# leds-and-button.net
KiCad netlist of a schematic drawn in EAGLE
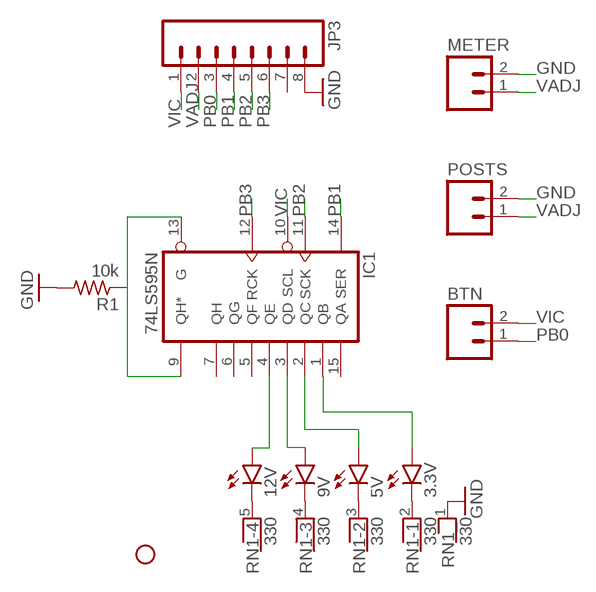
[diagram p0: schematic, sheet 1]

(export (version "E")
  (design (tool "Eeschema 10.0.6"))
  (components
    (comp (ref "3.3V")
      (value "LED3MM")
      (footprint "eagle-import:LED3MM")
      (libsource (lib "eagle-import") (part "LED3MM"))
    )
    (comp (ref "5V")
      (value "LED3MM")
      (footprint "eagle-import:LED3MM")
      (libsource (lib "eagle-import") (part "LED3MM"))
    )
    (comp (ref "9V")
      (value "LED3MM")
      (footprint "eagle-import:LED3MM")
      (libsource (lib "eagle-import") (part "LED3MM"))
    )
    (comp (ref "12V")
      (value "LED3MM")
      (footprint "eagle-import:LED3MM")
      (libsource (lib "eagle-import") (part "LED3MM"))
    )
    (comp (ref "BTN")
      (value "M02PTH")
      (footprint "eagle-import:1X02")
      (libsource (lib "eagle-import") (part "M02PTH"))
    )
    (comp (ref "IC1")
      (value "74LS595N")
      (footprint "eagle-import:DIL16")
      (libsource (lib "eagle-import") (part "74595NLS"))
    )
    (comp (ref "JP2")
      (value "STAND-OFF")
      (footprint "eagle-import:STAND-OFF")
      (libsource (lib "eagle-import") (part "STAND-OFF"))
    )
    (comp (ref "JP3")
      (value "M081X08")
      (footprint "eagle-import:1X08")
      (libsource (lib "eagle-import") (part "M081X08"))
    )
    (comp (ref "METER")
      (value "M02PTH")
      (footprint "eagle-import:1X02")
      (libsource (lib "eagle-import") (part "M02PTH"))
    )
    (comp (ref "POSTS")
      (value "M02PTH")
      (footprint "eagle-import:1X02")
      (libsource (lib "eagle-import") (part "M02PTH"))
    )
    (comp (ref "R1")
      (value "10k")
      (footprint "eagle-import:0204V")
      (libsource (lib "eagle-import") (part "R-US_0204/2V"))
    )
    (comp (ref "RN1")
      (value "330")
      (footprint "eagle-import:RN-6")
      (libsource (lib "eagle-import") (part "RNX5"))
    )
  )
  (nets
    (net (code "1") (name "/PB0") (class "Default")
      (node (ref "BTN") (pin "1") (pinfunction "1_1") (pintype "passive"))
      (node (ref "JP3") (pin "3") (pinfunction "3_3") (pintype "passive"))
    )
    (net (code "2") (name "/PB1") (class "Default")
      (node (ref "IC1") (pin "14") (pinfunction "SER_14") (pintype "input"))
      (node (ref "JP3") (pin "4") (pinfunction "4_4") (pintype "passive"))
    )
    (net (code "3") (name "/PB2") (class "Default")
      (node (ref "IC1") (pin "11") (pinfunction "SCK_11") (pintype "input"))
      (node (ref "JP3") (pin "5") (pinfunction "5_5") (pintype "passive"))
    )
    (net (code "4") (name "/PB3") (class "Default")
      (node (ref "IC1") (pin "12") (pinfunction "RCK_12") (pintype "input"))
      (node (ref "JP3") (pin "6") (pinfunction "6_6") (pintype "passive"))
    )
    (net (code "5") (name "/VADJ") (class "Default")
      (node (ref "JP3") (pin "2") (pinfunction "2_2") (pintype "passive"))
      (node (ref "METER") (pin "1") (pinfunction "1_1") (pintype "passive"))
      (node (ref "POSTS") (pin "1") (pinfunction "1_1") (pintype "passive"))
    )
    (net (code "6") (name "/VIC") (class "Default")
      (node (ref "BTN") (pin "2") (pinfunction "2_2") (pintype "passive"))
      (node (ref "IC1") (pin "10") (pinfunction "SCL_10") (pintype "input"))
      (node (ref "JP3") (pin "1") (pinfunction "1_1") (pintype "passive"))
    )
    (net (code "7") (name "GND") (class "Default")
      (node (ref "JP3") (pin "8") (pinfunction "8_8") (pintype "passive"))
      (node (ref "METER") (pin "2") (pinfunction "2_2") (pintype "passive"))
      (node (ref "POSTS") (pin "2") (pinfunction "2_2") (pintype "passive"))
      (node (ref "R1") (pin "2") (pinfunction "2_2") (pintype "passive"))
      (node (ref "RN1") (pin "1") (pinfunction "1_1") (pintype "passive"))
    )
    (net (code "8") (name "Net-(3.3V-C)") (class "Default")
      (node (ref "3.3V") (pin "K") (pinfunction "C_K") (pintype "passive"))
      (node (ref "RN1") (pin "2") (pinfunction "1_2") (pintype "passive"))
    )
    (net (code "9") (name "Net-(5V-C)") (class "Default")
      (node (ref "5V") (pin "K") (pinfunction "C_K") (pintype "passive"))
      (node (ref "RN1") (pin "3") (pinfunction "1_3") (pintype "passive"))
    )
    (net (code "10") (name "Net-(9V-C)") (class "Default")
      (node (ref "9V") (pin "K") (pinfunction "C_K") (pintype "passive"))
      (node (ref "RN1") (pin "4") (pinfunction "1_4") (pintype "passive"))
    )
    (net (code "11") (name "Net-(12V-C)") (class "Default")
      (node (ref "12V") (pin "K") (pinfunction "C_K") (pintype "passive"))
      (node (ref "RN1") (pin "5") (pinfunction "1_5") (pintype "passive"))
    )
    (net (code "12") (name "Net-(IC1A-G)") (class "Default")
      (node (ref "IC1") (pin "13") (pinfunction "G_13") (pintype "input"))
      (node (ref "IC1") (pin "9") (pinfunction "QH*_9") (pintype "tri_state"))
      (node (ref "R1") (pin "1") (pinfunction "1_1") (pintype "passive"))
    )
    (net (code "13") (name "Net-(IC1A-QB)") (class "Default")
      (node (ref "3.3V") (pin "A") (pinfunction "A_A") (pintype "passive"))
      (node (ref "IC1") (pin "1") (pinfunction "QB_1") (pintype "tri_state"))
    )
    (net (code "14") (name "Net-(IC1A-QC)") (class "Default")
      (node (ref "5V") (pin "A") (pinfunction "A_A") (pintype "passive"))
      (node (ref "IC1") (pin "2") (pinfunction "QC_2") (pintype "tri_state"))
    )
    (net (code "15") (name "Net-(IC1A-QD)") (class "Default")
      (node (ref "9V") (pin "A") (pinfunction "A_A") (pintype "passive"))
      (node (ref "IC1") (pin "3") (pinfunction "QD_3") (pintype "tri_state"))
    )
    (net (code "16") (name "Net-(IC1A-QE)") (class "Default")
      (node (ref "12V") (pin "A") (pinfunction "A_A") (pintype "passive"))
      (node (ref "IC1") (pin "4") (pinfunction "QE_4") (pintype "tri_state"))
    )
    (net (code "17") (name "unconnected-(IC1A-QA-Pad15)") (class "Default")
      (node (ref "IC1") (pin "15") (pinfunction "QA_15") (pintype "tri_state"))
    )
    (net (code "18") (name "unconnected-(IC1A-QF-Pad5)") (class "Default")
      (node (ref "IC1") (pin "5") (pinfunction "QF_5") (pintype "tri_state"))
    )
    (net (code "19") (name "unconnected-(IC1A-QG-Pad6)") (class "Default")
      (node (ref "IC1") (pin "6") (pinfunction "QG_6") (pintype "tri_state"))
    )
    (net (code "20") (name "unconnected-(IC1A-QH-Pad7)") (class "Default")
      (node (ref "IC1") (pin "7") (pinfunction "QH_7") (pintype "tri_state"))
    )
    (net (code "21") (name "unconnected-(JP3-Pad7)") (class "Default")
      (node (ref "JP3") (pin "7") (pinfunction "7_7") (pintype "passive"))
    )
  )
)
